# POWER.net
KiCad netlist of a schematic drawn in Altium Designer
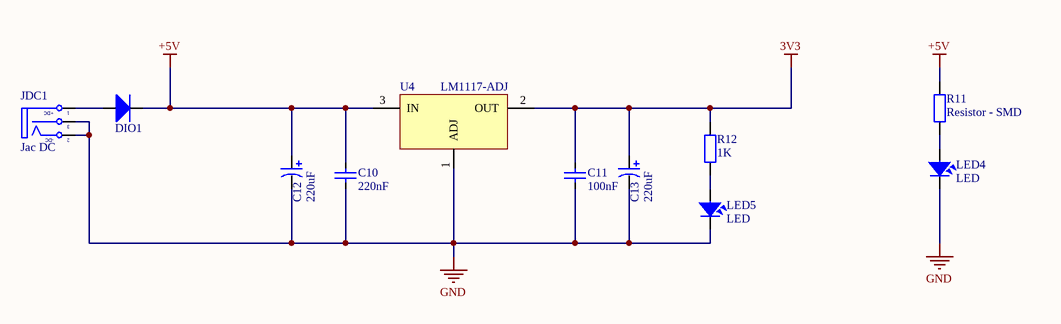
[diagram p0: POWER.SchDoc]

(export (version "E")
  (design (tool "Eeschema 10.0.6"))
  (components
    (comp (ref "C10")
      (value "220nF")
      (footprint "CAP_0805")
      (description "Capacitor")
      (fields (field (name "PUBLISHER") "Altium Limited"))
      (libsource (lib "My Library") (part "CapSMD"))
    )
    (comp (ref "C11")
      (value "100nF")
      (footprint "CAP_0805")
      (description "Capacitor")
      (fields (field (name "PUBLISHER") "Altium Limited"))
      (libsource (lib "My Library") (part "CapSMD"))
    )
    (comp (ref "C12")
      (value "220uF")
      (footprint "CAP_7343")
      (description "Polazied Tantalum Capacitor")
      (libsource (lib "My Library") (part "CAP_TAN_SMD"))
    )
    (comp (ref "C13")
      (value "220uF")
      (footprint "CAP_7343")
      (description "Polazied Tantalum Capacitor")
      (libsource (lib "My Library") (part "CAP_TAN_SMD"))
    )
    (comp (ref "DIO1")
      (value "Diode SMD")
      (footprint "DIO-214AC(SMA)")
      (description "Default Diode")
      (fields (field (name "PUBLISHER") "Altium Limited"))
      (libsource (lib "My Library") (part "Diode SMD"))
    )
    (comp (ref "JDC1")
      (value "Jac DC")
      (footprint "DC-IN")
      (description "Jac DC input")
      (libsource (lib "My Library") (part "DCIN"))
    )
    (comp (ref "LED4")
      (value "LED")
      (footprint "LED-0805-Blue")
      (description "LED Single colour Green and Red")
      (libsource (lib "My Library") (part "LED"))
    )
    (comp (ref "LED5")
      (value "LED")
      (footprint "LED-0805-Red")
      (description "LED Single colour Green and Red")
      (libsource (lib "My Library") (part "LED"))
    )
    (comp (ref "R11")
      (value "Resistor - SMD")
      (footprint "RES-SMD-0805")
      (description "Resistor SMD")
      (fields
        (field (name "MANUFACTURER") "Generic Components")
        (field (name "PUBLISHER") "Altium Hobart Technology Centre")
      )
      (libsource (lib "My Library") (part "Resistor - SMD"))
    )
    (comp (ref "R12")
      (value "1K")
      (footprint "RES-SMD-0805")
      (description "Resistor SMD")
      (fields
        (field (name "MANUFACTURER") "Generic Components")
        (field (name "PUBLISHER") "Altium Hobart Technology Centre")
      )
      (libsource (lib "My Library") (part "Resistor - SMD"))
    )
    (comp (ref "U4")
      (value "LM1117-ADJ")
      (footprint "LM1117-SOP")
      (description "800mA Low-Dropout Linear Regulator")
      (fields (field (name "CREATOR") "Nguyen Ba Bien"))
      (libsource (lib "My Library") (part "LM1117-ADJ"))
    )
  )
  (nets
    (net (code "1") (name "+5V") (class "Default")
      (node (ref "C10") (pin "2") (pinfunction "2_2") (pintype "passive"))
      (node (ref "C12") (pin "1") (pinfunction "1_1") (pintype "passive"))
      (node (ref "DIO1") (pin "2") (pinfunction "K_2") (pintype "passive"))
      (node (ref "R11") (pin "1") (pinfunction "1_1") (pintype "passive"))
      (node (ref "U4") (pin "3") (pinfunction "IN_3") (pintype "passive"))
    )
    (net (code "2") (name "3V3") (class "Default")
      (node (ref "C11") (pin "2") (pinfunction "2_2") (pintype "passive"))
      (node (ref "C13") (pin "1") (pinfunction "1_1") (pintype "passive"))
      (node (ref "R12") (pin "1") (pinfunction "1_1") (pintype "passive"))
      (node (ref "U4") (pin "2") (pinfunction "OUT_2") (pintype "passive"))
    )
    (net (code "3") (name "GND") (class "Default")
      (node (ref "C10") (pin "1") (pinfunction "1_1") (pintype "passive"))
      (node (ref "C11") (pin "1") (pinfunction "1_1") (pintype "passive"))
      (node (ref "C12") (pin "2") (pinfunction "2_2") (pintype "passive"))
      (node (ref "C13") (pin "2") (pinfunction "2_2") (pintype "passive"))
      (node (ref "JDC1") (pin "2") (pinfunction "TN_2") (pintype "passive"))
      (node (ref "JDC1") (pin "3") (pinfunction "S_3") (pintype "power_in"))
      (node (ref "LED4") (pin "2") (pinfunction "2_2") (pintype "passive"))
      (node (ref "LED5") (pin "2") (pinfunction "2_2") (pintype "passive"))
      (node (ref "U4") (pin "1") (pinfunction "ADJ_1") (pintype "passive"))
    )
    (net (code "4") (name "Net-(DIO1-A)") (class "Default")
      (node (ref "DIO1") (pin "1") (pinfunction "A_1") (pintype "passive"))
      (node (ref "JDC1") (pin "1") (pinfunction "T_1") (pintype "passive"))
    )
    (net (code "5") (name "Net-(LED4-Pad1)") (class "Default")
      (node (ref "LED4") (pin "1") (pinfunction "1_1") (pintype "passive"))
      (node (ref "R11") (pin "2") (pinfunction "2_2") (pintype "passive"))
    )
    (net (code "6") (name "Net-(LED5-Pad1)") (class "Default")
      (node (ref "LED5") (pin "1") (pinfunction "1_1") (pintype "passive"))
      (node (ref "R12") (pin "2") (pinfunction "2_2") (pintype "passive"))
    )
  )
)
